# lcd_duffle_pth_mk_1.net
KiCad netlist of a schematic drawn in EAGLE
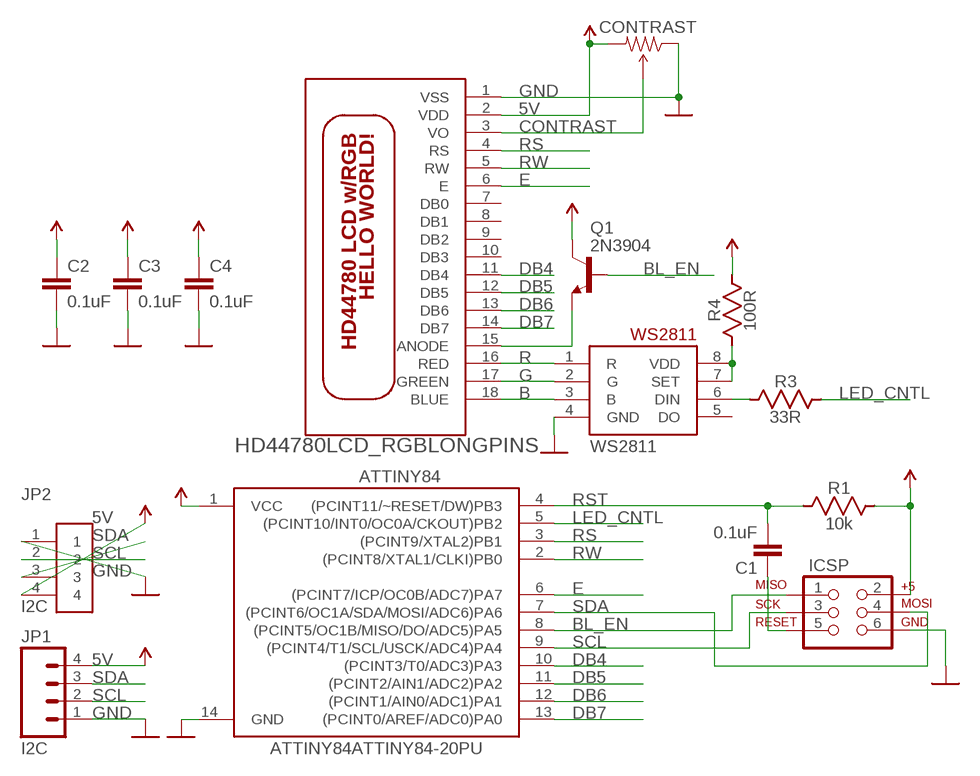
[diagram p0: schematic, sheet 1]

(export (version "E")
  (design (tool "Eeschema 10.0.6"))
  (components
    (comp (ref "ATTINY84")
      (value "ATTINY84ATTINY84-20PU")
      (footprint "eagle-import:DIL14")
      (libsource (lib "eagle-import") (part "ATTINY84ATTINY84-20PU"))
    )
    (comp (ref "C1")
      (value "0.1uF")
      (footprint "eagle-import:C025-024X044")
      (libsource (lib "eagle-import") (part "CAPACITOR-CERAMIC025-024X044"))
    )
    (comp (ref "C2")
      (value "0.1uF")
      (footprint "eagle-import:C025-024X044")
      (libsource (lib "eagle-import") (part "CAPACITOR-CERAMIC025-024X044"))
    )
    (comp (ref "C3")
      (value "0.1uF")
      (footprint "eagle-import:C025-024X044")
      (libsource (lib "eagle-import") (part "CAPACITOR-CERAMIC025-024X044"))
    )
    (comp (ref "C4")
      (value "0.1uF")
      (footprint "eagle-import:C025-024X044")
      (libsource (lib "eagle-import") (part "CAPACITOR-CERAMIC025-024X044"))
    )
    (comp (ref "CONTRAST")
      (value "TRIMPOT3362U-2")
      (footprint "eagle-import:3362U-2")
      (libsource (lib "eagle-import") (part "TRIMPOT3362U-2"))
    )
    (comp (ref "ICSP")
      (value "AVR_SPI_PRG_6PTH")
      (footprint "eagle-import:2X3")
      (libsource (lib "eagle-import") (part "AVR_SPI_PRG_6PTH"))
    )
    (comp (ref "JP1")
      (value "I2C")
      (footprint "eagle-import:MOLEX-1X4")
      (libsource (lib "eagle-import") (part "M04POLAR"))
    )
    (comp (ref "JP2")
      (value "I2C")
      (footprint "eagle-import:1X04-BIG")
      (libsource (lib "eagle-import") (part "1X4-BIG"))
    )
    (comp (ref "Q1")
      (value "2N3904")
      (footprint "eagle-import:TO-92-AMMO")
      (libsource (lib "eagle-import") (part "TRANSISTOR_NPNTO-92-AMMO"))
    )
    (comp (ref "R1")
      (value "10k")
      (footprint "eagle-import:AXIAL-PTH-5.08MM")
      (libsource (lib "eagle-import") (part "RESISTOR_PTH_0.2"))
    )
    (comp (ref "R3")
      (value "33R")
      (footprint "eagle-import:AXIAL-PTH-5.08MM")
      (libsource (lib "eagle-import") (part "RESISTOR_PTH_0.2"))
    )
    (comp (ref "R4")
      (value "100R")
      (footprint "eagle-import:AXIAL-PTH-5.08MM")
      (libsource (lib "eagle-import") (part "RESISTOR_PTH_0.2"))
    )
    (comp (ref "U$1")
      (value "HD44780LCD_RGBLONGPINS")
      (footprint "eagle-import:LCD1602-RGB")
      (libsource (lib "eagle-import") (part "HD44780LCD_RGBLONGPINS"))
    )
    (comp (ref "WS2811")
      (value "WS2811-SOP8")
      (footprint "eagle-import:SO08-SKINNYPADS")
      (libsource (lib "eagle-import") (part "WS2811-SOP8"))
    )
  )
  (nets
    (net (code "1") (name "/B") (class "Default")
      (node (ref "U$1") (pin "18") (pinfunction "BLUE_18") (pintype "input"))
      (node (ref "WS2811") (pin "3") (pinfunction "B_3") (pintype "open_collector"))
    )
    (net (code "2") (name "/BL_EN") (class "Default")
      (node (ref "ATTINY84") (pin "8") (pinfunction "(PCINT5/OC1B/MISO/DO/ADC5)PA5_8") (pintype "bidirectional"))
      (node (ref "ICSP") (pin "1") (pinfunction "1_1") (pintype "passive"))
      (node (ref "Q1") (pin "2") (pinfunction "B_2") (pintype "passive"))
    )
    (net (code "3") (name "/CONTRAST") (class "Default")
      (node (ref "CONTRAST") (pin "2") (pinfunction "WIPER_2") (pintype "passive"))
      (node (ref "U$1") (pin "3") (pinfunction "VO_3") (pintype "input"))
    )
    (net (code "4") (name "/DB4") (class "Default")
      (node (ref "ATTINY84") (pin "10") (pinfunction "(PCINT3/T0/ADC3)PA3_10") (pintype "bidirectional"))
      (node (ref "U$1") (pin "11") (pinfunction "DB4_11") (pintype "bidirectional"))
    )
    (net (code "5") (name "/DB5") (class "Default")
      (node (ref "ATTINY84") (pin "11") (pinfunction "(PCINT2/AIN1/ADC2)PA2_11") (pintype "bidirectional"))
      (node (ref "U$1") (pin "12") (pinfunction "DB5_12") (pintype "bidirectional"))
    )
    (net (code "6") (name "/DB6") (class "Default")
      (node (ref "ATTINY84") (pin "12") (pinfunction "(PCINT1/AIN0/ADC1)PA1_12") (pintype "bidirectional"))
      (node (ref "U$1") (pin "13") (pinfunction "DB6_13") (pintype "bidirectional"))
    )
    (net (code "7") (name "/DB7") (class "Default")
      (node (ref "ATTINY84") (pin "13") (pinfunction "(PCINT0/AREF/ADC0)PA0_13") (pintype "bidirectional"))
      (node (ref "U$1") (pin "14") (pinfunction "DB7_14") (pintype "bidirectional"))
    )
    (net (code "8") (name "/E") (class "Default")
      (node (ref "ATTINY84") (pin "6") (pinfunction "(PCINT7/ICP/OC0B/ADC7)PA7_6") (pintype "bidirectional"))
      (node (ref "U$1") (pin "6") (pinfunction "E_6") (pintype "input"))
    )
    (net (code "9") (name "/G") (class "Default")
      (node (ref "U$1") (pin "17") (pinfunction "GREEN_17") (pintype "input"))
      (node (ref "WS2811") (pin "2") (pinfunction "G_2") (pintype "open_collector"))
    )
    (net (code "10") (name "/LED_CNTL") (class "Default")
      (node (ref "ATTINY84") (pin "5") (pinfunction "(PCINT10/INT0/OC0A/CKOUT)PB2_5") (pintype "bidirectional"))
      (node (ref "R3") (pin "P$1") (pinfunction "2_P$1") (pintype "passive"))
    )
    (net (code "11") (name "/R") (class "Default")
      (node (ref "U$1") (pin "16") (pinfunction "RED_16") (pintype "input"))
      (node (ref "WS2811") (pin "1") (pinfunction "R_1") (pintype "open_collector"))
    )
    (net (code "12") (name "/RS") (class "Default")
      (node (ref "ATTINY84") (pin "3") (pinfunction "(PCINT9/XTAL2)PB1_3") (pintype "bidirectional"))
      (node (ref "U$1") (pin "4") (pinfunction "RS_4") (pintype "input"))
    )
    (net (code "13") (name "/RST") (class "Default")
      (node (ref "ATTINY84") (pin "4") (pinfunction "(PCINT11/~{RESET/DW})PB3_4") (pintype "bidirectional"))
      (node (ref "C1") (pin "2") (pinfunction "2_2") (pintype "passive"))
      (node (ref "R1") (pin "P$2") (pinfunction "1_P$2") (pintype "passive"))
    )
    (net (code "14") (name "/RW") (class "Default")
      (node (ref "ATTINY84") (pin "2") (pinfunction "(PCINT8/XTAL1/CLKI)PB0_2") (pintype "bidirectional"))
      (node (ref "U$1") (pin "5") (pinfunction "RW_5") (pintype "input"))
    )
    (net (code "15") (name "/SCL") (class "Default")
      (node (ref "ATTINY84") (pin "9") (pinfunction "(PCINT4/T1/SCL/USCK/ADC4)PA4_9") (pintype "bidirectional"))
      (node (ref "ICSP") (pin "3") (pinfunction "3_3") (pintype "passive"))
      (node (ref "JP1") (pin "2") (pinfunction "2_2") (pintype "passive"))
      (node (ref "JP2") (pin "2") (pinfunction "2_2") (pintype "bidirectional"))
    )
    (net (code "16") (name "/SDA") (class "Default")
      (node (ref "ATTINY84") (pin "7") (pinfunction "(PCINT6/OC1A/SDA/MOSI/ADC6)PA6_7") (pintype "bidirectional"))
      (node (ref "ICSP") (pin "4") (pinfunction "4_4") (pintype "passive"))
      (node (ref "JP1") (pin "3") (pinfunction "3_3") (pintype "passive"))
      (node (ref "JP2") (pin "3") (pinfunction "3_3") (pintype "bidirectional"))
    )
    (net (code "17") (name "5V") (class "Default")
      (node (ref "ATTINY84") (pin "1") (pinfunction "VCC_1") (pintype "bidirectional"))
      (node (ref "C2") (pin "2") (pinfunction "2_2") (pintype "passive"))
      (node (ref "C3") (pin "2") (pinfunction "2_2") (pintype "passive"))
      (node (ref "C4") (pin "2") (pinfunction "2_2") (pintype "passive"))
      (node (ref "CONTRAST") (pin "3") (pinfunction "CW_3") (pintype "passive"))
      (node (ref "ICSP") (pin "2") (pinfunction "2_2") (pintype "passive"))
      (node (ref "JP1") (pin "4") (pinfunction "4_4") (pintype "passive"))
      (node (ref "JP2") (pin "4") (pinfunction "4_4") (pintype "bidirectional"))
      (node (ref "Q1") (pin "3") (pinfunction "C_3") (pintype "passive"))
      (node (ref "R1") (pin "P$1") (pinfunction "2_P$1") (pintype "passive"))
      (node (ref "R4") (pin "P$1") (pinfunction "2_P$1") (pintype "passive"))
      (node (ref "U$1") (pin "2") (pinfunction "VDD_2") (pintype "power_in"))
    )
    (net (code "18") (name "GND") (class "Default")
      (node (ref "ATTINY84") (pin "14") (pinfunction "GND_14") (pintype "bidirectional"))
      (node (ref "C2") (pin "1") (pinfunction "1_1") (pintype "passive"))
      (node (ref "C3") (pin "1") (pinfunction "1_1") (pintype "passive"))
      (node (ref "C4") (pin "1") (pinfunction "1_1") (pintype "passive"))
      (node (ref "CONTRAST") (pin "1") (pinfunction "CCW_1") (pintype "passive"))
      (node (ref "ICSP") (pin "6") (pinfunction "6_6") (pintype "passive"))
      (node (ref "JP1") (pin "1") (pinfunction "1_1") (pintype "passive"))
      (node (ref "JP2") (pin "1") (pinfunction "1_1") (pintype "bidirectional"))
      (node (ref "U$1") (pin "1") (pinfunction "VSS_1") (pintype "power_in"))
      (node (ref "WS2811") (pin "4") (pinfunction "GND_4") (pintype "power_in"))
    )
    (net (code "19") (name "Net-(C1-Pad1)") (class "Default")
      (node (ref "C1") (pin "1") (pinfunction "1_1") (pintype "passive"))
      (node (ref "ICSP") (pin "5") (pinfunction "5_5") (pintype "passive"))
    )
    (net (code "20") (name "Net-(Q1-E)") (class "Default")
      (node (ref "Q1") (pin "1") (pinfunction "E_1") (pintype "passive"))
      (node (ref "U$1") (pin "15") (pinfunction "ANODE_15") (pintype "input"))
    )
    (net (code "21") (name "Net-(R3-1)") (class "Default")
      (node (ref "R3") (pin "P$2") (pinfunction "1_P$2") (pintype "passive"))
      (node (ref "WS2811") (pin "6") (pinfunction "DIN_6") (pintype "input"))
    )
    (net (code "22") (name "Net-(R4-1)") (class "Default")
      (node (ref "R4") (pin "P$2") (pinfunction "1_P$2") (pintype "passive"))
      (node (ref "WS2811") (pin "7") (pinfunction "SET_7") (pintype "input"))
      (node (ref "WS2811") (pin "8") (pinfunction "VDD_8") (pintype "power_in"))
    )
    (net (code "23") (name "unconnected-(U$1-DB0-Pad7)") (class "Default")
      (node (ref "U$1") (pin "7") (pinfunction "DB0_7") (pintype "bidirectional"))
    )
    (net (code "24") (name "unconnected-(U$1-DB1-Pad8)") (class "Default")
      (node (ref "U$1") (pin "8") (pinfunction "DB1_8") (pintype "bidirectional"))
    )
    (net (code "25") (name "unconnected-(U$1-DB2-Pad9)") (class "Default")
      (node (ref "U$1") (pin "9") (pinfunction "DB2_9") (pintype "bidirectional"))
    )
    (net (code "26") (name "unconnected-(U$1-DB3-Pad10)") (class "Default")
      (node (ref "U$1") (pin "10") (pinfunction "DB3_10") (pintype "bidirectional"))
    )
    (net (code "27") (name "unconnected-(WS2811-DO-Pad5)") (class "Default")
      (node (ref "WS2811") (pin "5") (pinfunction "DO_5") (pintype "output"))
    )
  )
)
